# OurEDA-P1K_usb.net
KiCad netlist of a schematic drawn in Altium Designer
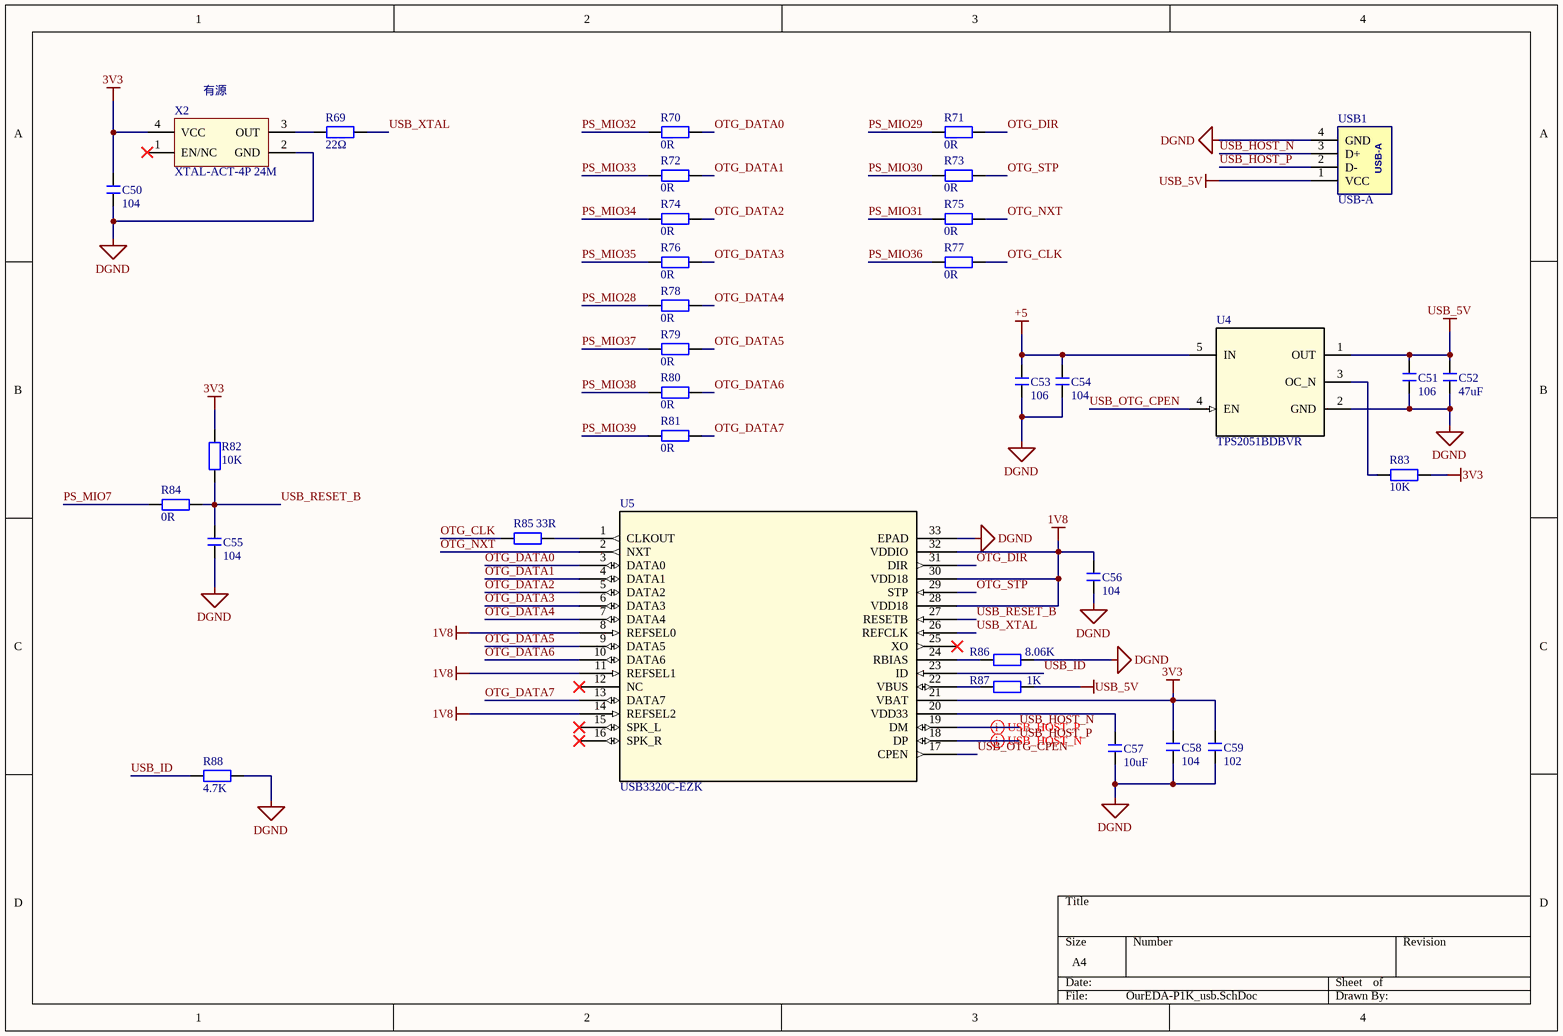
[diagram p0: OurEDA-P1K_usb.SchDoc]

(export (version "E")
  (design (tool "Eeschema 10.0.6"))
  (components
    (comp (ref "C50")
      (value "104")
      (footprint "C 0603_L")
      (description "无极性贴片电容")
      (fields (field (name "版权归属") "源创客"))
      (libsource (lib "3.1   - 电阻-电容-电感") (part "C"))
    )
    (comp (ref "C51")
      (value "106")
      (footprint "C 0603_L")
      (description "无极性贴片电容")
      (fields (field (name "版权归属") "源创客"))
      (libsource (lib "3.1   - 电阻-电容-电感") (part "C"))
    )
    (comp (ref "C52")
      (value "47uF")
      (footprint "C 0603_L")
      (description "无极性贴片电容")
      (fields (field (name "版权归属") "源创客"))
      (libsource (lib "3.1   - 电阻-电容-电感") (part "C"))
    )
    (comp (ref "C53")
      (value "106")
      (footprint "C 0603_L")
      (description "无极性贴片电容")
      (fields (field (name "版权归属") "源创客"))
      (libsource (lib "3.1   - 电阻-电容-电感") (part "C"))
    )
    (comp (ref "C54")
      (value "104")
      (footprint "C 0603_L")
      (description "无极性贴片电容")
      (fields (field (name "版权归属") "源创客"))
      (libsource (lib "3.1   - 电阻-电容-电感") (part "C"))
    )
    (comp (ref "C55")
      (value "104")
      (footprint "C 0603_L")
      (description "无极性贴片电容")
      (fields (field (name "版权归属") "源创客"))
      (libsource (lib "3.1   - 电阻-电容-电感") (part "C"))
    )
    (comp (ref "C56")
      (value "104")
      (footprint "C 0603_L")
      (description "无极性贴片电容")
      (fields (field (name "版权归属") "源创客"))
      (libsource (lib "3.1   - 电阻-电容-电感") (part "C"))
    )
    (comp (ref "C57")
      (value "10uF")
      (footprint "C 0603_L")
      (description "无极性贴片电容")
      (fields (field (name "版权归属") "源创客"))
      (libsource (lib "3.1   - 电阻-电容-电感") (part "C"))
    )
    (comp (ref "C58")
      (value "104")
      (footprint "C 0603_L")
      (description "无极性贴片电容")
      (fields (field (name "版权归属") "源创客"))
      (libsource (lib "3.1   - 电阻-电容-电感") (part "C"))
    )
    (comp (ref "C59")
      (value "102")
      (footprint "C 0603_L")
      (description "无极性贴片电容")
      (fields (field (name "版权归属") "源创客"))
      (libsource (lib "3.1   - 电阻-电容-电感") (part "C"))
    )
    (comp (ref "R69")
      (value "22Ω")
      (footprint "R 0603_L")
      (description "贴片电阻")
      (fields (field (name "版权归属") "源创客"))
      (libsource (lib "3.1   - 电阻-电容-电感") (part "R"))
    )
    (comp (ref "R70")
      (value "0R")
      (footprint "R 0603_L")
      (description "贴片电阻")
      (fields (field (name "版权归属") "源创客"))
      (libsource (lib "3.1   - 电阻-电容-电感") (part "R"))
    )
    (comp (ref "R71")
      (value "0R")
      (footprint "R 0603_L")
      (description "贴片电阻")
      (fields (field (name "版权归属") "源创客"))
      (libsource (lib "3.1   - 电阻-电容-电感") (part "R"))
    )
    (comp (ref "R72")
      (value "0R")
      (footprint "R 0603_L")
      (description "贴片电阻")
      (fields (field (name "版权归属") "源创客"))
      (libsource (lib "3.1   - 电阻-电容-电感") (part "R"))
    )
    (comp (ref "R73")
      (value "0R")
      (footprint "R 0603_L")
      (description "贴片电阻")
      (fields (field (name "版权归属") "源创客"))
      (libsource (lib "3.1   - 电阻-电容-电感") (part "R"))
    )
    (comp (ref "R74")
      (value "0R")
      (footprint "R 0603_L")
      (description "贴片电阻")
      (fields (field (name "版权归属") "源创客"))
      (libsource (lib "3.1   - 电阻-电容-电感") (part "R"))
    )
    (comp (ref "R75")
      (value "0R")
      (footprint "R 0603_L")
      (description "贴片电阻")
      (fields (field (name "版权归属") "源创客"))
      (libsource (lib "3.1   - 电阻-电容-电感") (part "R"))
    )
    (comp (ref "R76")
      (value "0R")
      (footprint "R 0603_L")
      (description "贴片电阻")
      (fields (field (name "版权归属") "源创客"))
      (libsource (lib "3.1   - 电阻-电容-电感") (part "R"))
    )
    (comp (ref "R77")
      (value "0R")
      (footprint "R 0603_L")
      (description "贴片电阻")
      (fields (field (name "版权归属") "源创客"))
      (libsource (lib "3.1   - 电阻-电容-电感") (part "R"))
    )
    (comp (ref "R78")
      (value "0R")
      (footprint "R 0603_L")
      (description "贴片电阻")
      (fields (field (name "版权归属") "源创客"))
      (libsource (lib "3.1   - 电阻-电容-电感") (part "R"))
    )
    (comp (ref "R79")
      (value "0R")
      (footprint "R 0603_L")
      (description "贴片电阻")
      (fields (field (name "版权归属") "源创客"))
      (libsource (lib "3.1   - 电阻-电容-电感") (part "R"))
    )
    (comp (ref "R80")
      (value "0R")
      (footprint "R 0603_L")
      (description "贴片电阻")
      (fields (field (name "版权归属") "源创客"))
      (libsource (lib "3.1   - 电阻-电容-电感") (part "R"))
    )
    (comp (ref "R81")
      (value "0R")
      (footprint "R 0603_L")
      (description "贴片电阻")
      (fields (field (name "版权归属") "源创客"))
      (libsource (lib "3.1   - 电阻-电容-电感") (part "R"))
    )
    (comp (ref "R82")
      (value "10K")
      (footprint "R 0603_L")
      (description "贴片电阻")
      (fields (field (name "版权归属") "源创客"))
      (libsource (lib "3.1   - 电阻-电容-电感") (part "R"))
    )
    (comp (ref "R83")
      (value "10K")
      (footprint "R 0603_L")
      (description "贴片电阻")
      (fields (field (name "版权归属") "源创客"))
      (libsource (lib "3.1   - 电阻-电容-电感") (part "R"))
    )
    (comp (ref "R84")
      (value "0R")
      (footprint "R 0603_L")
      (description "贴片电阻")
      (fields (field (name "版权归属") "源创客"))
      (libsource (lib "3.1   - 电阻-电容-电感") (part "R"))
    )
    (comp (ref "R85")
      (value "33R")
      (footprint "R 0603_L")
      (description "贴片电阻")
      (fields (field (name "版权归属") "源创客"))
      (libsource (lib "3.1   - 电阻-电容-电感") (part "R"))
    )
    (comp (ref "R86")
      (value "8.06K")
      (footprint "R 0603_L")
      (description "贴片电阻")
      (fields (field (name "版权归属") "源创客"))
      (libsource (lib "3.1   - 电阻-电容-电感") (part "R"))
    )
    (comp (ref "R87")
      (value "1K")
      (footprint "R 0603_L")
      (description "贴片电阻")
      (fields (field (name "版权归属") "源创客"))
      (libsource (lib "3.1   - 电阻-电容-电感") (part "R"))
    )
    (comp (ref "R88")
      (value "4.7K")
      (footprint "R 0603_L")
      (description "贴片电阻")
      (fields (field (name "版权归属") "源创客"))
      (libsource (lib "3.1   - 电阻-电容-电感") (part "R"))
    )
    (comp (ref "U4")
      (value "TPS2051BDBVR")
      (footprint "DBV0005A_N")
      (description "No Description Available")
      (fields
        (field (name "ALTERNATE_PARTNUMBER") "TPS2051BDBVT")
        (field (name "MANUFACTURER") "Texas Instruments")
        (field (name "COPYRIGHT") "Copyright (C) 2022 Ultra Librarian. All rights reserved.")
      )
      (libsource (lib "MySchLib") (part "TPS2051BDBVR"))
    )
    (comp (ref "U5")
      (value "USB3320C-EZK")
      (footprint "QFN32_5X5MC_MCH")
      (description "No Description Available")
      (fields (field (name "COPYRIGHT") "Copyright (C) 2022 Ultra Librarian. All rights reserved."))
      (libsource (lib "MySchLib") (part "USB3320C-EZK"))
    )
    (comp (ref "USB1") (value "USB-A") (footprint "USB-A/S_F") (libsource (lib "USB连接器") (part "USB-A")))
    (comp (ref "X2")
      (value "XTAL-ACT-4P 24M")
      (footprint "OSC 1612-4P")
      (description "4脚有源晶振")
      (libsource (lib "晶振") (part "XTAL-ACT-4P"))
    )
  )
  (nets
    (net (code "1") (name "+5") (class "Default")
      (node (ref "C53") (pin "2") (pinfunction "2_2") (pintype "passive"))
      (node (ref "C54") (pin "2") (pinfunction "2_2") (pintype "passive"))
      (node (ref "U4") (pin "5") (pinfunction "IN_5") (pintype "power_in"))
    )
    (net (code "2") (name "/OTG_CLK") (class "Default")
      (node (ref "R77") (pin "1") (pinfunction "1_1") (pintype "passive"))
      (node (ref "R85") (pin "1") (pinfunction "1_1") (pintype "passive"))
    )
    (net (code "3") (name "/OTG_DATA0") (class "Default")
      (node (ref "R70") (pin "1") (pinfunction "1_1") (pintype "passive"))
      (node (ref "U5") (pin "3") (pinfunction "DATA0_3") (pintype "bidirectional"))
    )
    (net (code "4") (name "/OTG_DATA1") (class "Default")
      (node (ref "R72") (pin "1") (pinfunction "1_1") (pintype "passive"))
      (node (ref "U5") (pin "4") (pinfunction "DATA1_4") (pintype "bidirectional"))
    )
    (net (code "5") (name "/OTG_DATA2") (class "Default")
      (node (ref "R74") (pin "1") (pinfunction "1_1") (pintype "passive"))
      (node (ref "U5") (pin "5") (pinfunction "DATA2_5") (pintype "bidirectional"))
    )
    (net (code "6") (name "/OTG_DATA3") (class "Default")
      (node (ref "R76") (pin "1") (pinfunction "1_1") (pintype "passive"))
      (node (ref "U5") (pin "6") (pinfunction "DATA3_6") (pintype "bidirectional"))
    )
    (net (code "7") (name "/OTG_DATA4") (class "Default")
      (node (ref "R78") (pin "1") (pinfunction "1_1") (pintype "passive"))
      (node (ref "U5") (pin "7") (pinfunction "DATA4_7") (pintype "bidirectional"))
    )
    (net (code "8") (name "/OTG_DATA5") (class "Default")
      (node (ref "R79") (pin "1") (pinfunction "1_1") (pintype "passive"))
      (node (ref "U5") (pin "9") (pinfunction "DATA5_9") (pintype "bidirectional"))
    )
    (net (code "9") (name "/OTG_DATA6") (class "Default")
      (node (ref "R80") (pin "1") (pinfunction "1_1") (pintype "passive"))
      (node (ref "U5") (pin "10") (pinfunction "DATA6_10") (pintype "bidirectional"))
    )
    (net (code "10") (name "/OTG_DATA7") (class "Default")
      (node (ref "R81") (pin "1") (pinfunction "1_1") (pintype "passive"))
      (node (ref "U5") (pin "13") (pinfunction "DATA7_13") (pintype "bidirectional"))
    )
    (net (code "11") (name "/OTG_DIR") (class "Default")
      (node (ref "R71") (pin "1") (pinfunction "1_1") (pintype "passive"))
      (node (ref "U5") (pin "31") (pinfunction "DIR_31") (pintype "output"))
    )
    (net (code "12") (name "/OTG_NXT") (class "Default")
      (node (ref "R75") (pin "1") (pinfunction "1_1") (pintype "passive"))
      (node (ref "U5") (pin "2") (pinfunction "NXT_2") (pintype "output"))
    )
    (net (code "13") (name "/OTG_STP") (class "Default")
      (node (ref "R73") (pin "1") (pinfunction "1_1") (pintype "passive"))
      (node (ref "U5") (pin "29") (pinfunction "STP_29") (pintype "input"))
    )
    (net (code "14") (name "/PS_MIO7") (class "Default")
      (node (ref "R84") (pin "2") (pinfunction "2_2") (pintype "passive"))
    )
    (net (code "15") (name "/PS_MIO28") (class "Default")
      (node (ref "R78") (pin "2") (pinfunction "2_2") (pintype "passive"))
    )
    (net (code "16") (name "/PS_MIO29") (class "Default")
      (node (ref "R71") (pin "2") (pinfunction "2_2") (pintype "passive"))
    )
    (net (code "17") (name "/PS_MIO30") (class "Default")
      (node (ref "R73") (pin "2") (pinfunction "2_2") (pintype "passive"))
    )
    (net (code "18") (name "/PS_MIO31") (class "Default")
      (node (ref "R75") (pin "2") (pinfunction "2_2") (pintype "passive"))
    )
    (net (code "19") (name "/PS_MIO32") (class "Default")
      (node (ref "R70") (pin "2") (pinfunction "2_2") (pintype "passive"))
    )
    (net (code "20") (name "/PS_MIO33") (class "Default")
      (node (ref "R72") (pin "2") (pinfunction "2_2") (pintype "passive"))
    )
    (net (code "21") (name "/PS_MIO34") (class "Default")
      (node (ref "R74") (pin "2") (pinfunction "2_2") (pintype "passive"))
    )
    (net (code "22") (name "/PS_MIO35") (class "Default")
      (node (ref "R76") (pin "2") (pinfunction "2_2") (pintype "passive"))
    )
    (net (code "23") (name "/PS_MIO36") (class "Default")
      (node (ref "R77") (pin "2") (pinfunction "2_2") (pintype "passive"))
    )
    (net (code "24") (name "/PS_MIO37") (class "Default")
      (node (ref "R79") (pin "2") (pinfunction "2_2") (pintype "passive"))
    )
    (net (code "25") (name "/PS_MIO38") (class "Default")
      (node (ref "R80") (pin "2") (pinfunction "2_2") (pintype "passive"))
    )
    (net (code "26") (name "/PS_MIO39") (class "Default")
      (node (ref "R81") (pin "2") (pinfunction "2_2") (pintype "passive"))
    )
    (net (code "27") (name "/USB_HOST_N") (class "Default")
      (node (ref "U5") (pin "19") (pinfunction "DM_19") (pintype "bidirectional"))
      (node (ref "USB1") (pin "3") (pinfunction "D+_3") (pintype "passive"))
    )
    (net (code "28") (name "/USB_HOST_P") (class "Default")
      (node (ref "U5") (pin "18") (pinfunction "DP_18") (pintype "bidirectional"))
      (node (ref "USB1") (pin "2") (pinfunction "D-_2") (pintype "passive"))
    )
    (net (code "29") (name "/USB_ID") (class "Default")
      (node (ref "R88") (pin "2") (pinfunction "2_2") (pintype "passive"))
      (node (ref "U5") (pin "23") (pinfunction "ID_23") (pintype "input"))
    )
    (net (code "30") (name "/USB_OTG_CPEN") (class "Default")
      (node (ref "U4") (pin "4") (pinfunction "EN_4") (pintype "input"))
      (node (ref "U5") (pin "17") (pinfunction "CPEN_17") (pintype "output"))
    )
    (net (code "31") (name "/USB_RESET_B") (class "Default")
      (node (ref "C55") (pin "2") (pinfunction "2_2") (pintype "passive"))
      (node (ref "R82") (pin "1") (pinfunction "1_1") (pintype "passive"))
      (node (ref "R84") (pin "1") (pinfunction "1_1") (pintype "passive"))
      (node (ref "U5") (pin "27") (pinfunction "RESETB_27") (pintype "input"))
    )
    (net (code "32") (name "/USB_XTAL") (class "Default")
      (node (ref "R69") (pin "2") (pinfunction "2_2") (pintype "passive"))
      (node (ref "U5") (pin "26") (pinfunction "REFCLK_26") (pintype "input"))
    )
    (net (code "33") (name "1V8") (class "Default")
      (node (ref "C56") (pin "2") (pinfunction "2_2") (pintype "passive"))
      (node (ref "U5") (pin "11") (pinfunction "REFSEL1_11") (pintype "input"))
      (node (ref "U5") (pin "14") (pinfunction "REFSEL2_14") (pintype "input"))
      (node (ref "U5") (pin "28") (pinfunction "VDD18_28") (pintype "power_in"))
      (node (ref "U5") (pin "30") (pinfunction "VDD18_30") (pintype "power_in"))
      (node (ref "U5") (pin "32") (pinfunction "VDDIO_32") (pintype "power_in"))
      (node (ref "U5") (pin "8") (pinfunction "REFSEL0_8") (pintype "input"))
    )
    (net (code "34") (name "3V3") (class "Default")
      (node (ref "C50") (pin "2") (pinfunction "2_2") (pintype "passive"))
      (node (ref "C58") (pin "2") (pinfunction "2_2") (pintype "passive"))
      (node (ref "C59") (pin "2") (pinfunction "2_2") (pintype "passive"))
      (node (ref "R82") (pin "2") (pinfunction "2_2") (pintype "passive"))
      (node (ref "R83") (pin "1") (pinfunction "1_1") (pintype "passive"))
      (node (ref "U5") (pin "21") (pinfunction "VBAT_21") (pintype "power_in"))
      (node (ref "X2") (pin "4") (pinfunction "VCC_4") (pintype "passive"))
    )
    (net (code "35") (name "DGND") (class "Default")
      (node (ref "C50") (pin "1") (pinfunction "1_1") (pintype "passive"))
      (node (ref "C51") (pin "1") (pinfunction "1_1") (pintype "passive"))
      (node (ref "C52") (pin "1") (pinfunction "1_1") (pintype "passive"))
      (node (ref "C53") (pin "1") (pinfunction "1_1") (pintype "passive"))
      (node (ref "C54") (pin "1") (pinfunction "1_1") (pintype "passive"))
      (node (ref "C55") (pin "1") (pinfunction "1_1") (pintype "passive"))
      (node (ref "C56") (pin "1") (pinfunction "1_1") (pintype "passive"))
      (node (ref "C57") (pin "1") (pinfunction "1_1") (pintype "passive"))
      (node (ref "C58") (pin "1") (pinfunction "1_1") (pintype "passive"))
      (node (ref "C59") (pin "1") (pinfunction "1_1") (pintype "passive"))
      (node (ref "R86") (pin "2") (pinfunction "2_2") (pintype "passive"))
      (node (ref "R88") (pin "1") (pinfunction "1_1") (pintype "passive"))
      (node (ref "U4") (pin "2") (pinfunction "GND_2") (pintype "power_in"))
      (node (ref "U5") (pin "33") (pinfunction "EPAD_33") (pintype "passive"))
      (node (ref "USB1") (pin "4") (pinfunction "GND_4") (pintype "passive"))
      (node (ref "X2") (pin "2") (pinfunction "GND_2") (pintype "passive"))
    )
    (net (code "36") (name "Net-(U4-OC_N)") (class "Default")
      (node (ref "R83") (pin "2") (pinfunction "2_2") (pintype "passive"))
      (node (ref "U4") (pin "3") (pinfunction "OC_N_3") (pintype "open_collector"))
    )
    (net (code "37") (name "Net-(U5-CLKOUT)") (class "Default")
      (node (ref "R85") (pin "2") (pinfunction "2_2") (pintype "passive"))
      (node (ref "U5") (pin "1") (pinfunction "CLKOUT_1") (pintype "output"))
    )
    (net (code "38") (name "Net-(U5-RBIAS)") (class "Default")
      (node (ref "R86") (pin "1") (pinfunction "1_1") (pintype "passive"))
      (node (ref "U5") (pin "24") (pinfunction "RBIAS_24") (pintype "passive"))
    )
    (net (code "39") (name "Net-(U5-VBUS)") (class "Default")
      (node (ref "R87") (pin "1") (pinfunction "1_1") (pintype "passive"))
      (node (ref "U5") (pin "22") (pinfunction "VBUS_22") (pintype "bidirectional"))
    )
    (net (code "40") (name "Net-(U5-VDD33)") (class "Default")
      (node (ref "C57") (pin "2") (pinfunction "2_2") (pintype "passive"))
      (node (ref "U5") (pin "20") (pinfunction "VDD33_20") (pintype "power_in"))
    )
    (net (code "41") (name "Net-(X2-OUT)") (class "Default")
      (node (ref "R69") (pin "1") (pinfunction "1_1") (pintype "passive"))
      (node (ref "X2") (pin "3") (pinfunction "OUT_3") (pintype "passive"))
    )
    (net (code "42") (name "USB_5V") (class "Default")
      (node (ref "C51") (pin "2") (pinfunction "2_2") (pintype "passive"))
      (node (ref "C52") (pin "2") (pinfunction "2_2") (pintype "passive"))
      (node (ref "R87") (pin "2") (pinfunction "2_2") (pintype "passive"))
      (node (ref "U4") (pin "1") (pinfunction "OUT_1") (pintype "power_in"))
      (node (ref "USB1") (pin "1") (pinfunction "VCC_1") (pintype "passive"))
    )
    (net (code "43") (name "unconnected-(U5-NC-Pad12)") (class "Default")
      (node (ref "U5") (pin "12") (pinfunction "NC_12") (pintype "passive+no_connect"))
    )
    (net (code "44") (name "unconnected-(U5-SPK_L-Pad15)") (class "Default")
      (node (ref "U5") (pin "15") (pinfunction "SPK_L_15") (pintype "bidirectional+no_connect"))
    )
    (net (code "45") (name "unconnected-(U5-SPK_R-Pad16)") (class "Default")
      (node (ref "U5") (pin "16") (pinfunction "SPK_R_16") (pintype "bidirectional+no_connect"))
    )
    (net (code "46") (name "unconnected-(U5-XO-Pad25)") (class "Default")
      (node (ref "U5") (pin "25") (pinfunction "XO_25") (pintype "output+no_connect"))
    )
    (net (code "47") (name "unconnected-(X2-EN{slash}NC-Pad1)") (class "Default")
      (node (ref "X2") (pin "1") (pinfunction "EN/NC_1") (pintype "passive+no_connect"))
    )
  )
)
